# H.net
KiCad netlist of a schematic drawn in Altium Designer
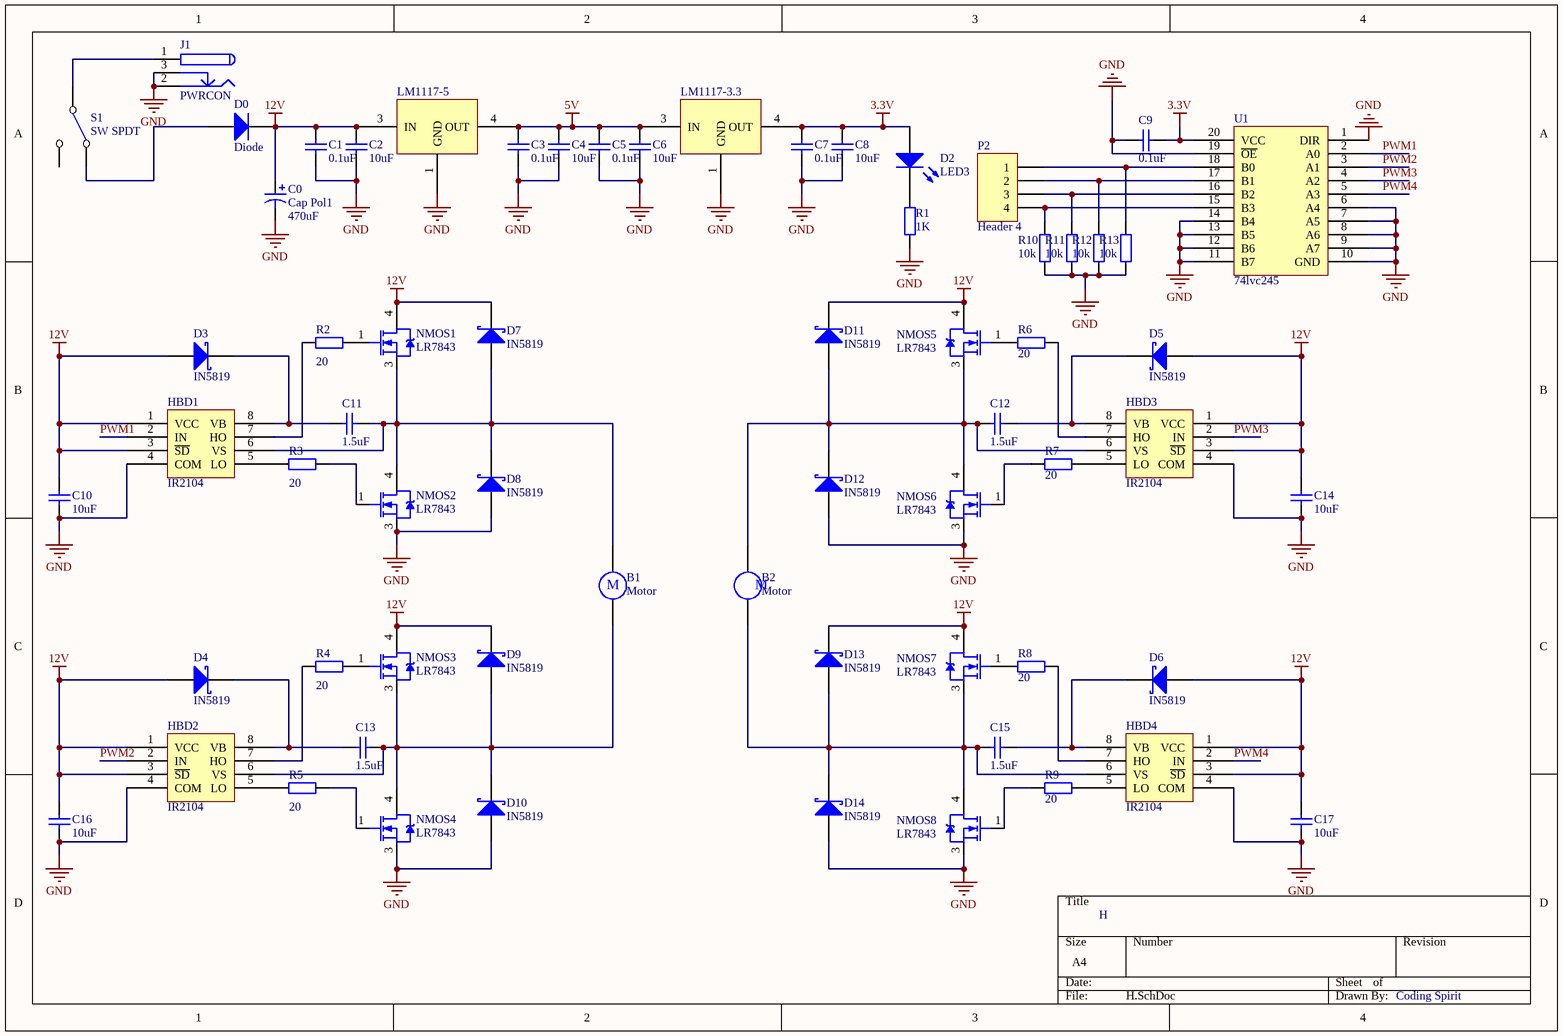
[diagram p0: H.SchDoc]

(export (version "E")
  (design (tool "Eeschema 10.0.6"))
  (components
    (comp (ref "B1")
      (value "Motor")
      (footprint "5_08")
      (description "Motor, General Kind")
      (fields (field (name "PUBLISHER") "Altium Limited"))
      (libsource (lib "Miscellaneous Devices (2)") (part "Motor"))
    )
    (comp (ref "B2")
      (value "Motor")
      (footprint "5_08")
      (description "Motor, General Kind")
      (fields (field (name "PUBLISHER") "Altium Limited"))
      (libsource (lib "Miscellaneous Devices (2)") (part "Motor"))
    )
    (comp (ref "C0")
      (value "Cap Pol1")
      (footprint "C-RB-SD10")
      (description "Polarized Capacitor (Radial)")
      (fields (field (name "ALTIUM_VALUE") "470uF") (field (name "PUBLISHER") "Altium Limited"))
      (libsource (lib "Miscellaneous Devices") (part "Cap Pol1"))
    )
    (comp (ref "C1")
      (value "0.1uF")
      (footprint "C-0603")
      (description "Capacitor (Semiconductor SIM Model)")
      (fields (field (name "Comment") "Cap") (field (name "PUBLISHER") "Altium Limited"))
      (libsource (lib "Miscellaneous Devices") (part "Cap Semi"))
    )
    (comp (ref "C2")
      (value "10uF")
      (footprint "C-0603")
      (description "Capacitor (Semiconductor SIM Model)")
      (fields (field (name "Comment") "Cap") (field (name "PUBLISHER") "Altium Limited"))
      (libsource (lib "Miscellaneous Devices") (part "Cap Semi"))
    )
    (comp (ref "C3")
      (value "0.1uF")
      (footprint "C-0603")
      (description "Capacitor (Semiconductor SIM Model)")
      (fields (field (name "Comment") "Cap") (field (name "PUBLISHER") "Altium Limited"))
      (libsource (lib "Miscellaneous Devices") (part "Cap Semi"))
    )
    (comp (ref "C4")
      (value "10uF")
      (footprint "C-0603")
      (description "Capacitor (Semiconductor SIM Model)")
      (fields (field (name "Comment") "Cap") (field (name "PUBLISHER") "Altium Limited"))
      (libsource (lib "Miscellaneous Devices") (part "Cap Semi"))
    )
    (comp (ref "C5")
      (value "0.1uF")
      (footprint "C-0603")
      (description "Capacitor (Semiconductor SIM Model)")
      (fields (field (name "Comment") "Cap") (field (name "PUBLISHER") "Altium Limited"))
      (libsource (lib "Miscellaneous Devices") (part "Cap Semi"))
    )
    (comp (ref "C6")
      (value "10uF")
      (footprint "C-0603")
      (description "Capacitor (Semiconductor SIM Model)")
      (fields (field (name "Comment") "Cap") (field (name "PUBLISHER") "Altium Limited"))
      (libsource (lib "Miscellaneous Devices") (part "Cap Semi"))
    )
    (comp (ref "C7")
      (value "0.1uF")
      (footprint "C-0603")
      (description "Capacitor (Semiconductor SIM Model)")
      (fields (field (name "Comment") "Cap") (field (name "PUBLISHER") "Altium Limited"))
      (libsource (lib "Miscellaneous Devices") (part "Cap Semi"))
    )
    (comp (ref "C8")
      (value "10uF")
      (footprint "C-0603")
      (description "Capacitor (Semiconductor SIM Model)")
      (fields (field (name "Comment") "Cap") (field (name "PUBLISHER") "Altium Limited"))
      (libsource (lib "Miscellaneous Devices") (part "Cap Semi"))
    )
    (comp (ref "C9")
      (value "0.1uF")
      (footprint "C-0603")
      (description "Capacitor (Semiconductor SIM Model)")
      (fields (field (name "Comment") "Cap") (field (name "PUBLISHER") "Altium Limited"))
      (libsource (lib "Miscellaneous Devices") (part "Cap Semi"))
    )
    (comp (ref "C10")
      (value "10uF")
      (footprint "C-0603")
      (description "Capacitor (Semiconductor SIM Model)")
      (fields (field (name "Comment") "Cap") (field (name "PUBLISHER") "Altium Limited"))
      (libsource (lib "Miscellaneous Devices") (part "Cap Semi"))
    )
    (comp (ref "C11")
      (value "1.5uF")
      (footprint "C-0603")
      (description "Capacitor (Semiconductor SIM Model)")
      (fields (field (name "Comment") "Cap") (field (name "PUBLISHER") "Altium Limited"))
      (libsource (lib "Miscellaneous Devices") (part "Cap Semi"))
    )
    (comp (ref "C12")
      (value "1.5uF")
      (footprint "C-0603")
      (description "Capacitor (Semiconductor SIM Model)")
      (fields (field (name "Comment") "Cap") (field (name "PUBLISHER") "Altium Limited"))
      (libsource (lib "Miscellaneous Devices") (part "Cap Semi"))
    )
    (comp (ref "C13")
      (value "1.5uF")
      (footprint "C-0603")
      (description "Capacitor (Semiconductor SIM Model)")
      (fields (field (name "Comment") "Cap") (field (name "PUBLISHER") "Altium Limited"))
      (libsource (lib "Miscellaneous Devices") (part "Cap Semi"))
    )
    (comp (ref "C14")
      (value "10uF")
      (footprint "C-0603")
      (description "Capacitor (Semiconductor SIM Model)")
      (fields (field (name "Comment") "Cap") (field (name "PUBLISHER") "Altium Limited"))
      (libsource (lib "Miscellaneous Devices") (part "Cap Semi"))
    )
    (comp (ref "C15")
      (value "1.5uF")
      (footprint "C-0603")
      (description "Capacitor (Semiconductor SIM Model)")
      (fields (field (name "Comment") "Cap") (field (name "PUBLISHER") "Altium Limited"))
      (libsource (lib "Miscellaneous Devices") (part "Cap Semi"))
    )
    (comp (ref "C16")
      (value "10uF")
      (footprint "C-0603")
      (description "Capacitor (Semiconductor SIM Model)")
      (fields (field (name "Comment") "Cap") (field (name "PUBLISHER") "Altium Limited"))
      (libsource (lib "Miscellaneous Devices") (part "Cap Semi"))
    )
    (comp (ref "C17")
      (value "10uF")
      (footprint "C-0603")
      (description "Capacitor (Semiconductor SIM Model)")
      (fields (field (name "Comment") "Cap") (field (name "PUBLISHER") "Altium Limited"))
      (libsource (lib "Miscellaneous Devices") (part "Cap Semi"))
    )
    (comp (ref "D0")
      (value "Diode")
      (footprint "SMA")
      (description "Default Diode")
      (fields (field (name "PUBLISHER") "Altium Limited"))
      (libsource (lib "Miscellaneous Devices") (part "Diode"))
    )
    (comp (ref "D2")
      (value "LED3")
      (footprint "DSO-C2/D5.6")
      (description "Typical BLUE SiC LED")
      (fields (field (name "PUBLISHER") "Altium Limited"))
      (libsource (lib "Miscellaneous Devices (2)") (part "LED3"))
    )
    (comp (ref "D3")
      (value "IN5819")
      (footprint "SMB-D")
      (description "Schottky Diode")
      (fields (field (name "PUBLISHER") "Altium Limited"))
      (libsource (lib "Miscellaneous Devices") (part "D Schottky"))
    )
    (comp (ref "D4")
      (value "IN5819")
      (footprint "SMB-D")
      (description "Schottky Diode")
      (fields (field (name "PUBLISHER") "Altium Limited"))
      (libsource (lib "Miscellaneous Devices") (part "D Schottky"))
    )
    (comp (ref "D5")
      (value "IN5819")
      (footprint "SMB-D")
      (description "Schottky Diode")
      (fields (field (name "PUBLISHER") "Altium Limited"))
      (libsource (lib "Miscellaneous Devices") (part "D Schottky"))
    )
    (comp (ref "D6")
      (value "IN5819")
      (footprint "SMB-D")
      (description "Schottky Diode")
      (fields (field (name "PUBLISHER") "Altium Limited"))
      (libsource (lib "Miscellaneous Devices") (part "D Schottky"))
    )
    (comp (ref "D7")
      (value "IN5819")
      (footprint "SMB-D")
      (description "Schottky Diode")
      (fields (field (name "PUBLISHER") "Altium Limited"))
      (libsource (lib "Miscellaneous Devices") (part "D Schottky"))
    )
    (comp (ref "D8")
      (value "IN5819")
      (footprint "SMB-D")
      (description "Schottky Diode")
      (fields (field (name "PUBLISHER") "Altium Limited"))
      (libsource (lib "Miscellaneous Devices") (part "D Schottky"))
    )
    (comp (ref "D9")
      (value "IN5819")
      (footprint "SMB-D")
      (description "Schottky Diode")
      (fields (field (name "PUBLISHER") "Altium Limited"))
      (libsource (lib "Miscellaneous Devices") (part "D Schottky"))
    )
    (comp (ref "D10")
      (value "IN5819")
      (footprint "SMB-D")
      (description "Schottky Diode")
      (fields (field (name "PUBLISHER") "Altium Limited"))
      (libsource (lib "Miscellaneous Devices") (part "D Schottky"))
    )
    (comp (ref "D11")
      (value "IN5819")
      (footprint "SMB-D")
      (description "Schottky Diode")
      (fields (field (name "PUBLISHER") "Altium Limited"))
      (libsource (lib "Miscellaneous Devices") (part "D Schottky"))
    )
    (comp (ref "D12")
      (value "IN5819")
      (footprint "SMB-D")
      (description "Schottky Diode")
      (fields (field (name "PUBLISHER") "Altium Limited"))
      (libsource (lib "Miscellaneous Devices") (part "D Schottky"))
    )
    (comp (ref "D13")
      (value "IN5819")
      (footprint "SMB-D")
      (description "Schottky Diode")
      (fields (field (name "PUBLISHER") "Altium Limited"))
      (libsource (lib "Miscellaneous Devices") (part "D Schottky"))
    )
    (comp (ref "D14")
      (value "IN5819")
      (footprint "SMB-D")
      (description "Schottky Diode")
      (fields (field (name "PUBLISHER") "Altium Limited"))
      (libsource (lib "Miscellaneous Devices") (part "D Schottky"))
    )
    (comp (ref "HBD1") (value "IR2104") (footprint "IR2104") (libsource (lib "") (part "IR2104_1")))
    (comp (ref "HBD2") (value "IR2104") (footprint "IR2104") (libsource (lib "") (part "IR2104_1")))
    (comp (ref "HBD3") (value "IR2104") (footprint "IR2104") (libsource (lib "MOS_H") (part "IR2104")))
    (comp (ref "HBD4") (value "IR2104") (footprint "IR2104") (libsource (lib "MOS_H") (part "IR2104")))
    (comp (ref "J1")
      (value "PWRCON")
      (footprint "DC-005")
      (description "直流电源端子")
      (fields (field (name "PUBLISHER") "Altium Limited"))
      (libsource (lib "HDR_fszhang") (part "PWRCON"))
    )
    (comp (ref "LM1117-3.3") (value "LM1117") (footprint "lm1117") (libsource (lib "MOS_H") (part "LM1117")))
    (comp (ref "LM1117-5") (value "LM1117") (footprint "lm1117") (libsource (lib "MOS_H") (part "LM1117")))
    (comp (ref "NMOS1") (value "LR7843") (footprint "IR7843") (libsource (lib "MOS_H") (part "IR7843")))
    (comp (ref "NMOS2") (value "LR7843") (footprint "IR7843") (libsource (lib "MOS_H") (part "IR7843")))
    (comp (ref "NMOS3") (value "LR7843") (footprint "IR7843") (libsource (lib "MOS_H") (part "IR7843")))
    (comp (ref "NMOS4") (value "LR7843") (footprint "IR7843") (libsource (lib "MOS_H") (part "IR7843")))
    (comp (ref "NMOS5") (value "LR7843") (footprint "IR7843") (libsource (lib "MOS_H") (part "IR7843")))
    (comp (ref "NMOS6") (value "LR7843") (footprint "IR7843") (libsource (lib "MOS_H") (part "IR7843")))
    (comp (ref "NMOS7") (value "LR7843") (footprint "IR7843") (libsource (lib "MOS_H") (part "IR7843")))
    (comp (ref "NMOS8") (value "LR7843") (footprint "IR7843") (libsource (lib "MOS_H") (part "IR7843")))
    (comp (ref "P2")
      (value "Header 4")
      (footprint "HDR1X4")
      (description "Header, 4-Pin")
      (fields (field (name "PUBLISHER") "Altium Limited"))
      (libsource (lib "Miscellaneous Connectors") (part "Header 4"))
    )
    (comp (ref "R1")
      (value "1K")
      (footprint "0603-1")
      (description "Resistor")
      (fields (field (name "Comment") "Res2") (field (name "PUBLISHER") "Altium Limited"))
      (libsource (lib "") (part "Res2_3"))
    )
    (comp (ref "R2")
      (value "20")
      (footprint "0603-1")
      (description "Resistor")
      (fields (field (name "Comment") "Res2") (field (name "PUBLISHER") "Altium Limited"))
      (libsource (lib "") (part "Res2_2"))
    )
    (comp (ref "R3")
      (value "20")
      (footprint "0603-1")
      (description "Resistor")
      (fields (field (name "Comment") "Res2") (field (name "PUBLISHER") "Altium Limited"))
      (libsource (lib "") (part "Res2_2"))
    )
    (comp (ref "R4")
      (value "20")
      (footprint "0603-1")
      (description "Resistor")
      (fields (field (name "Comment") "Res2") (field (name "PUBLISHER") "Altium Limited"))
      (libsource (lib "") (part "Res2_2"))
    )
    (comp (ref "R5")
      (value "20")
      (footprint "0603-1")
      (description "Resistor")
      (fields (field (name "Comment") "Res2") (field (name "PUBLISHER") "Altium Limited"))
      (libsource (lib "") (part "Res2_2"))
    )
    (comp (ref "R6")
      (value "20")
      (footprint "0603-1")
      (description "Resistor")
      (fields (field (name "Comment") "Res2") (field (name "PUBLISHER") "Altium Limited"))
      (libsource (lib "") (part "Res2_1"))
    )
    (comp (ref "R7")
      (value "20")
      (footprint "0603-1")
      (description "Resistor")
      (fields (field (name "Comment") "Res2") (field (name "PUBLISHER") "Altium Limited"))
      (libsource (lib "") (part "Res2_1"))
    )
    (comp (ref "R8")
      (value "20")
      (footprint "0603-1")
      (description "Resistor")
      (fields (field (name "Comment") "Res2") (field (name "PUBLISHER") "Altium Limited"))
      (libsource (lib "") (part "Res2_1"))
    )
    (comp (ref "R9")
      (value "20")
      (footprint "0603-1")
      (description "Resistor")
      (fields (field (name "Comment") "Res2") (field (name "PUBLISHER") "Altium Limited"))
      (libsource (lib "") (part "Res2_1"))
    )
    (comp (ref "R10")
      (value "10k")
      (footprint "0603-1")
      (description "Resistor")
      (fields (field (name "Comment") "Res2") (field (name "PUBLISHER") "Altium Limited"))
      (libsource (lib "Miscellaneous Devices") (part "Res2"))
    )
    (comp (ref "R11")
      (value "10k")
      (footprint "0603-1")
      (description "Resistor")
      (fields (field (name "Comment") "Res2") (field (name "PUBLISHER") "Altium Limited"))
      (libsource (lib "Miscellaneous Devices") (part "Res2"))
    )
    (comp (ref "R12")
      (value "10k")
      (footprint "0603-1")
      (description "Resistor")
      (fields (field (name "Comment") "Res2") (field (name "PUBLISHER") "Altium Limited"))
      (libsource (lib "Miscellaneous Devices") (part "Res2"))
    )
    (comp (ref "R13")
      (value "10k")
      (footprint "0603-1")
      (description "Resistor")
      (fields (field (name "Comment") "Res2") (field (name "PUBLISHER") "Altium Limited"))
      (libsource (lib "Miscellaneous Devices") (part "Res2"))
    )
    (comp (ref "S1") (value "SW SPDT") (footprint "SW3P") (libsource (lib "MOS_H") (part "SW SPDT")))
    (comp (ref "U1") (value "74lvc245") (footprint "TSSOP-20") (libsource (lib "MOS_H") (part "74lvc245")))
  )
  (nets
    (net (code "1") (name "/PWM1") (class "Default")
      (node (ref "HBD1") (pin "2") (pinfunction "IN_2") (pintype "passive"))
      (node (ref "U1") (pin "2") (pinfunction "A0_2") (pintype "passive"))
    )
    (net (code "2") (name "/PWM2") (class "Default")
      (node (ref "HBD2") (pin "2") (pinfunction "IN_2") (pintype "passive"))
      (node (ref "U1") (pin "3") (pinfunction "A1_3") (pintype "passive"))
    )
    (net (code "3") (name "/PWM3") (class "Default")
      (node (ref "HBD3") (pin "2") (pinfunction "IN_2") (pintype "passive"))
      (node (ref "U1") (pin "4") (pinfunction "A2_4") (pintype "passive"))
    )
    (net (code "4") (name "/PWM4") (class "Default")
      (node (ref "HBD4") (pin "2") (pinfunction "IN_2") (pintype "passive"))
      (node (ref "U1") (pin "5") (pinfunction "A3_5") (pintype "passive"))
    )
    (net (code "5") (name "3.3V") (class "Default")
      (node (ref "C7") (pin "2") (pinfunction "2_2") (pintype "passive"))
      (node (ref "C8") (pin "2") (pinfunction "2_2") (pintype "passive"))
      (node (ref "C9") (pin "1") (pinfunction "1_1") (pintype "passive"))
      (node (ref "D2") (pin "1") (pinfunction "A_1") (pintype "passive"))
      (node (ref "LM1117-3.3") (pin "4") (pinfunction "OUT_4") (pintype "passive"))
      (node (ref "U1") (pin "20") (pinfunction "VCC_20") (pintype "passive"))
    )
    (net (code "6") (name "5V") (class "Default")
      (node (ref "C3") (pin "2") (pinfunction "2_2") (pintype "passive"))
      (node (ref "C4") (pin "2") (pinfunction "2_2") (pintype "passive"))
      (node (ref "C5") (pin "2") (pinfunction "2_2") (pintype "passive"))
      (node (ref "C6") (pin "2") (pinfunction "2_2") (pintype "passive"))
      (node (ref "LM1117-3.3") (pin "3") (pinfunction "IN_3") (pintype "passive"))
      (node (ref "LM1117-5") (pin "4") (pinfunction "OUT_4") (pintype "passive"))
    )
    (net (code "7") (name "12V") (class "Default")
      (node (ref "C0") (pin "1") (pinfunction "1_1") (pintype "passive"))
      (node (ref "C1") (pin "2") (pinfunction "2_2") (pintype "passive"))
      (node (ref "C10") (pin "1") (pinfunction "1_1") (pintype "passive"))
      (node (ref "C14") (pin "1") (pinfunction "1_1") (pintype "passive"))
      (node (ref "C16") (pin "1") (pinfunction "1_1") (pintype "passive"))
      (node (ref "C17") (pin "1") (pinfunction "1_1") (pintype "passive"))
      (node (ref "C2") (pin "2") (pinfunction "2_2") (pintype "passive"))
      (node (ref "D0") (pin "2") (pinfunction "K_2") (pintype "passive"))
      (node (ref "D11") (pin "2") (pinfunction "K_2") (pintype "passive"))
      (node (ref "D13") (pin "2") (pinfunction "K_2") (pintype "passive"))
      (node (ref "D3") (pin "1") (pinfunction "A_1") (pintype "passive"))
      (node (ref "D4") (pin "1") (pinfunction "A_1") (pintype "passive"))
      (node (ref "D5") (pin "1") (pinfunction "A_1") (pintype "passive"))
      (node (ref "D6") (pin "1") (pinfunction "A_1") (pintype "passive"))
      (node (ref "D7") (pin "2") (pinfunction "K_2") (pintype "passive"))
      (node (ref "D9") (pin "2") (pinfunction "K_2") (pintype "passive"))
      (node (ref "HBD1") (pin "1") (pinfunction "VCC_1") (pintype "passive"))
      (node (ref "HBD1") (pin "3") (pinfunction "~{SD}_3") (pintype "passive"))
      (node (ref "HBD2") (pin "1") (pinfunction "VCC_1") (pintype "passive"))
      (node (ref "HBD2") (pin "3") (pinfunction "~{SD}_3") (pintype "passive"))
      (node (ref "HBD3") (pin "1") (pinfunction "VCC_1") (pintype "passive"))
      (node (ref "HBD3") (pin "3") (pinfunction "~{SD}_3") (pintype "passive"))
      (node (ref "HBD4") (pin "1") (pinfunction "VCC_1") (pintype "passive"))
      (node (ref "HBD4") (pin "3") (pinfunction "~{SD}_3") (pintype "passive"))
      (node (ref "LM1117-5") (pin "3") (pinfunction "IN_3") (pintype "passive"))
      (node (ref "NMOS1") (pin "4") (pinfunction "D_4") (pintype "passive"))
      (node (ref "NMOS3") (pin "4") (pinfunction "D_4") (pintype "passive"))
      (node (ref "NMOS5") (pin "4") (pinfunction "D_4") (pintype "passive"))
      (node (ref "NMOS7") (pin "4") (pinfunction "D_4") (pintype "passive"))
    )
    (net (code "8") (name "GND") (class "Default")
      (node (ref "C0") (pin "2") (pinfunction "2_2") (pintype "passive"))
      (node (ref "C1") (pin "1") (pinfunction "1_1") (pintype "passive"))
      (node (ref "C10") (pin "2") (pinfunction "2_2") (pintype "passive"))
      (node (ref "C14") (pin "2") (pinfunction "2_2") (pintype "passive"))
      (node (ref "C16") (pin "2") (pinfunction "2_2") (pintype "passive"))
      (node (ref "C17") (pin "2") (pinfunction "2_2") (pintype "passive"))
      (node (ref "C2") (pin "1") (pinfunction "1_1") (pintype "passive"))
      (node (ref "C3") (pin "1") (pinfunction "1_1") (pintype "passive"))
      (node (ref "C4") (pin "1") (pinfunction "1_1") (pintype "passive"))
      (node (ref "C5") (pin "1") (pinfunction "1_1") (pintype "passive"))
      (node (ref "C6") (pin "1") (pinfunction "1_1") (pintype "passive"))
      (node (ref "C7") (pin "1") (pinfunction "1_1") (pintype "passive"))
      (node (ref "C8") (pin "1") (pinfunction "1_1") (pintype "passive"))
      (node (ref "C9") (pin "2") (pinfunction "2_2") (pintype "passive"))
      (node (ref "D10") (pin "1") (pinfunction "A_1") (pintype "passive"))
      (node (ref "D12") (pin "1") (pinfunction "A_1") (pintype "passive"))
      (node (ref "D14") (pin "1") (pinfunction "A_1") (pintype "passive"))
      (node (ref "D8") (pin "1") (pinfunction "A_1") (pintype "passive"))
      (node (ref "HBD1") (pin "4") (pinfunction "COM_4") (pintype "passive"))
      (node (ref "HBD2") (pin "4") (pinfunction "COM_4") (pintype "passive"))
      (node (ref "HBD3") (pin "4") (pinfunction "COM_4") (pintype "passive"))
      (node (ref "HBD4") (pin "4") (pinfunction "COM_4") (pintype "passive"))
      (node (ref "J1") (pin "2") (pinfunction "2_2") (pintype "power_in"))
      (node (ref "J1") (pin "3") (pinfunction "3_3") (pintype "power_in"))
      (node (ref "LM1117-3.3") (pin "1") (pinfunction "GND_1") (pintype "passive"))
      (node (ref "LM1117-5") (pin "1") (pinfunction "GND_1") (pintype "passive"))
      (node (ref "NMOS2") (pin "3") (pinfunction "S_3") (pintype "passive"))
      (node (ref "NMOS4") (pin "3") (pinfunction "S_3") (pintype "passive"))
      (node (ref "NMOS6") (pin "3") (pinfunction "S_3") (pintype "passive"))
      (node (ref "NMOS8") (pin "3") (pinfunction "S_3") (pintype "passive"))
      (node (ref "R1") (pin "1") (pinfunction "1_1") (pintype "passive"))
      (node (ref "R10") (pin "2") (pinfunction "2_2") (pintype "passive"))
      (node (ref "R11") (pin "2") (pinfunction "2_2") (pintype "passive"))
      (node (ref "R12") (pin "2") (pinfunction "2_2") (pintype "passive"))
      (node (ref "R13") (pin "2") (pinfunction "2_2") (pintype "passive"))
      (node (ref "U1") (pin "1") (pinfunction "DIR_1") (pintype "passive"))
      (node (ref "U1") (pin "10") (pinfunction "GND_10") (pintype "passive"))
      (node (ref "U1") (pin "11") (pinfunction "B7_11") (pintype "passive"))
      (node (ref "U1") (pin "12") (pinfunction "B6_12") (pintype "passive"))
      (node (ref "U1") (pin "13") (pinfunction "B5_13") (pintype "passive"))
      (node (ref "U1") (pin "14") (pinfunction "B4_14") (pintype "passive"))
      (node (ref "U1") (pin "19") (pinfunction "~{OE}_19") (pintype "passive"))
      (node (ref "U1") (pin "6") (pinfunction "A4_6") (pintype "passive"))
      (node (ref "U1") (pin "7") (pinfunction "A5_7") (pintype "passive"))
      (node (ref "U1") (pin "8") (pinfunction "A6_8") (pintype "passive"))
      (node (ref "U1") (pin "9") (pinfunction "A7_9") (pintype "passive"))
    )
    (net (code "9") (name "Net-(D0-A)") (class "Default")
      (node (ref "D0") (pin "1") (pinfunction "A_1") (pintype "passive"))
      (node (ref "S1") (pin "2") (pinfunction "NC_2") (pintype "passive"))
    )
    (net (code "10") (name "Net-(D2-K)") (class "Default")
      (node (ref "D2") (pin "2") (pinfunction "K_2") (pintype "passive"))
      (node (ref "R1") (pin "2") (pinfunction "2_2") (pintype "passive"))
    )
    (net (code "11") (name "Net-(D3-K)") (class "Default")
      (node (ref "C11") (pin "1") (pinfunction "1_1") (pintype "passive"))
      (node (ref "D3") (pin "2") (pinfunction "K_2") (pintype "passive"))
      (node (ref "HBD1") (pin "8") (pinfunction "VB_8") (pintype "passive"))
    )
    (net (code "12") (name "Net-(D4-K)") (class "Default")
      (node (ref "C13") (pin "1") (pinfunction "1_1") (pintype "passive"))
      (node (ref "D4") (pin "2") (pinfunction "K_2") (pintype "passive"))
      (node (ref "HBD2") (pin "8") (pinfunction "VB_8") (pintype "passive"))
    )
    (net (code "13") (name "Net-(D5-K)") (class "Default")
      (node (ref "C12") (pin "1") (pinfunction "1_1") (pintype "passive"))
      (node (ref "D5") (pin "2") (pinfunction "K_2") (pintype "passive"))
      (node (ref "HBD3") (pin "8") (pinfunction "VB_8") (pintype "passive"))
    )
    (net (code "14") (name "Net-(D6-K)") (class "Default")
      (node (ref "C15") (pin "1") (pinfunction "1_1") (pintype "passive"))
      (node (ref "D6") (pin "2") (pinfunction "K_2") (pintype "passive"))
      (node (ref "HBD4") (pin "8") (pinfunction "VB_8") (pintype "passive"))
    )
    (net (code "15") (name "Net-(D7-A)") (class "Default")
      (node (ref "B1") (pin "1") (pinfunction "1_1") (pintype "passive"))
      (node (ref "C11") (pin "2") (pinfunction "2_2") (pintype "passive"))
      (node (ref "D7") (pin "1") (pinfunction "A_1") (pintype "passive"))
      (node (ref "D8") (pin "2") (pinfunction "K_2") (pintype "passive"))
      (node (ref "HBD1") (pin "6") (pinfunction "VS_6") (pintype "passive"))
      (node (ref "NMOS1") (pin "3") (pinfunction "S_3") (pintype "passive"))
      (node (ref "NMOS2") (pin "4") (pinfunction "D_4") (pintype "passive"))
    )
    (net (code "16") (name "Net-(D10-K)") (class "Default")
      (node (ref "B1") (pin "2") (pinfunction "2_2") (pintype "passive"))
      (node (ref "C13") (pin "2") (pinfunction "2_2") (pintype "passive"))
      (node (ref "D10") (pin "2") (pinfunction "K_2") (pintype "passive"))
      (node (ref "D9") (pin "1") (pinfunction "A_1") (pintype "passive"))
      (node (ref "HBD2") (pin "6") (pinfunction "VS_6") (pintype "passive"))
      (node (ref "NMOS3") (pin "3") (pinfunction "S_3") (pintype "passive"))
      (node (ref "NMOS4") (pin "4") (pinfunction "D_4") (pintype "passive"))
    )
    (net (code "17") (name "Net-(D11-A)") (class "Default")
      (node (ref "B2") (pin "1") (pinfunction "1_1") (pintype "passive"))
      (node (ref "C12") (pin "2") (pinfunction "2_2") (pintype "passive"))
      (node (ref "D11") (pin "1") (pinfunction "A_1") (pintype "passive"))
      (node (ref "D12") (pin "2") (pinfunction "K_2") (pintype "passive"))
      (node (ref "HBD3") (pin "6") (pinfunction "VS_6") (pintype "passive"))
      (node (ref "NMOS5") (pin "3") (pinfunction "S_3") (pintype "passive"))
      (node (ref "NMOS6") (pin "4") (pinfunction "D_4") (pintype "passive"))
    )
    (net (code "18") (name "Net-(D13-A)") (class "Default")
      (node (ref "B2") (pin "2") (pinfunction "2_2") (pintype "passive"))
      (node (ref "C15") (pin "2") (pinfunction "2_2") (pintype "passive"))
      (node (ref "D13") (pin "1") (pinfunction "A_1") (pintype "passive"))
      (node (ref "D14") (pin "2") (pinfunction "K_2") (pintype "passive"))
      (node (ref "HBD4") (pin "6") (pinfunction "VS_6") (pintype "passive"))
      (node (ref "NMOS7") (pin "3") (pinfunction "S_3") (pintype "passive"))
      (node (ref "NMOS8") (pin "4") (pinfunction "D_4") (pintype "passive"))
    )
    (net (code "19") (name "Net-(HBD1-HO)") (class "Default")
      (node (ref "HBD1") (pin "7") (pinfunction "HO_7") (pintype "passive"))
      (node (ref "R2") (pin "1") (pinfunction "1_1") (pintype "passive"))
    )
    (net (code "20") (name "Net-(HBD1-LO)") (class "Default")
      (node (ref "HBD1") (pin "5") (pinfunction "LO_5") (pintype "passive"))
      (node (ref "R3") (pin "1") (pinfunction "1_1") (pintype "passive"))
    )
    (net (code "21") (name "Net-(HBD2-HO)") (class "Default")
      (node (ref "HBD2") (pin "7") (pinfunction "HO_7") (pintype "passive"))
      (node (ref "R4") (pin "1") (pinfunction "1_1") (pintype "passive"))
    )
    (net (code "22") (name "Net-(HBD2-LO)") (class "Default")
      (node (ref "HBD2") (pin "5") (pinfunction "LO_5") (pintype "passive"))
      (node (ref "R5") (pin "1") (pinfunction "1_1") (pintype "passive"))
    )
    (net (code "23") (name "Net-(HBD3-HO)") (class "Default")
      (node (ref "HBD3") (pin "7") (pinfunction "HO_7") (pintype "passive"))
      (node (ref "R6") (pin "1") (pinfunction "1_1") (pintype "passive"))
    )
    (net (code "24") (name "Net-(HBD3-LO)") (class "Default")
      (node (ref "HBD3") (pin "5") (pinfunction "LO_5") (pintype "passive"))
      (node (ref "R7") (pin "1") (pinfunction "1_1") (pintype "passive"))
    )
    (net (code "25") (name "Net-(HBD4-HO)") (class "Default")
      (node (ref "HBD4") (pin "7") (pinfunction "HO_7") (pintype "passive"))
      (node (ref "R8") (pin "1") (pinfunction "1_1") (pintype "passive"))
    )
    (net (code "26") (name "Net-(HBD4-LO)") (class "Default")
      (node (ref "HBD4") (pin "5") (pinfunction "LO_5") (pintype "passive"))
      (node (ref "R9") (pin "1") (pinfunction "1_1") (pintype "passive"))
    )
    (net (code "27") (name "Net-(NMOS1-G)") (class "Default")
      (node (ref "NMOS1") (pin "1") (pinfunction "G_1") (pintype "passive"))
      (node (ref "R2") (pin "2") (pinfunction "2_2") (pintype "passive"))
    )
    (net (code "28") (name "Net-(NMOS2-G)") (class "Default")
      (node (ref "NMOS2") (pin "1") (pinfunction "G_1") (pintype "passive"))
      (node (ref "R3") (pin "2") (pinfunction "2_2") (pintype "passive"))
    )
    (net (code "29") (name "Net-(NMOS3-G)") (class "Default")
      (node (ref "NMOS3") (pin "1") (pinfunction "G_1") (pintype "passive"))
      (node (ref "R4") (pin "2") (pinfunction "2_2") (pintype "passive"))
    )
    (net (code "30") (name "Net-(NMOS4-G)") (class "Default")
      (node (ref "NMOS4") (pin "1") (pinfunction "G_1") (pintype "passive"))
      (node (ref "R5") (pin "2") (pinfunction "2_2") (pintype "passive"))
    )
    (net (code "31") (name "Net-(NMOS5-G)") (class "Default")
      (node (ref "NMOS5") (pin "1") (pinfunction "G_1") (pintype "passive"))
      (node (ref "R6") (pin "2") (pinfunction "2_2") (pintype "passive"))
    )
    (net (code "32") (name "Net-(NMOS6-G)") (class "Default")
      (node (ref "NMOS6") (pin "1") (pinfunction "G_1") (pintype "passive"))
      (node (ref "R7") (pin "2") (pinfunction "2_2") (pintype "passive"))
    )
    (net (code "33") (name "Net-(NMOS7-G)") (class "Default")
      (node (ref "NMOS7") (pin "1") (pinfunction "G_1") (pintype "passive"))
      (node (ref "R8") (pin "2") (pinfunction "2_2") (pintype "passive"))
    )
    (net (code "34") (name "Net-(NMOS8-G)") (class "Default")
      (node (ref "NMOS8") (pin "1") (pinfunction "G_1") (pintype "passive"))
      (node (ref "R9") (pin "2") (pinfunction "2_2") (pintype "passive"))
    )
    (net (code "35") (name "Net-(S1-COMMON)") (class "Default")
      (node (ref "J1") (pin "1") (pinfunction "1_1") (pintype "power_in"))
      (node (ref "S1") (pin "1") (pinfunction "COMMON_1") (pintype "passive"))
    )
    (net (code "36") (name "Net-(U1-B0)") (class "Default")
      (node (ref "P2") (pin "1") (pinfunction "1_1") (pintype "passive"))
      (node (ref "R13") (pin "1") (pinfunction "1_1") (pintype "passive"))
      (node (ref "U1") (pin "18") (pinfunction "B0_18") (pintype "passive"))
    )
    (net (code "37") (name "Net-(U1-B1)") (class "Default")
      (node (ref "P2") (pin "2") (pinfunction "2_2") (pintype "passive"))
      (node (ref "R12") (pin "1") (pinfunction "1_1") (pintype "passive"))
      (node (ref "U1") (pin "17") (pinfunction "B1_17") (pintype "passive"))
    )
    (net (code "38") (name "Net-(U1-B2)") (class "Default")
      (node (ref "P2") (pin "3") (pinfunction "3_3") (pintype "passive"))
      (node (ref "R11") (pin "1") (pinfunction "1_1") (pintype "passive"))
      (node (ref "U1") (pin "16") (pinfunction "B2_16") (pintype "passive"))
    )
    (net (code "39") (name "Net-(U1-B3)") (class "Default")
      (node (ref "P2") (pin "4") (pinfunction "4_4") (pintype "passive"))
      (node (ref "R10") (pin "1") (pinfunction "1_1") (pintype "passive"))
      (node (ref "U1") (pin "15") (pinfunction "B3_15") (pintype "passive"))
    )
    (net (code "40") (name "unconnected-(S1-NO-Pad3)") (class "Default")
      (node (ref "S1") (pin "3") (pinfunction "NO_3") (pintype "passive"))
    )
  )
)
